# voice_caller.net
KiCad netlist of a schematic drawn in EAGLE
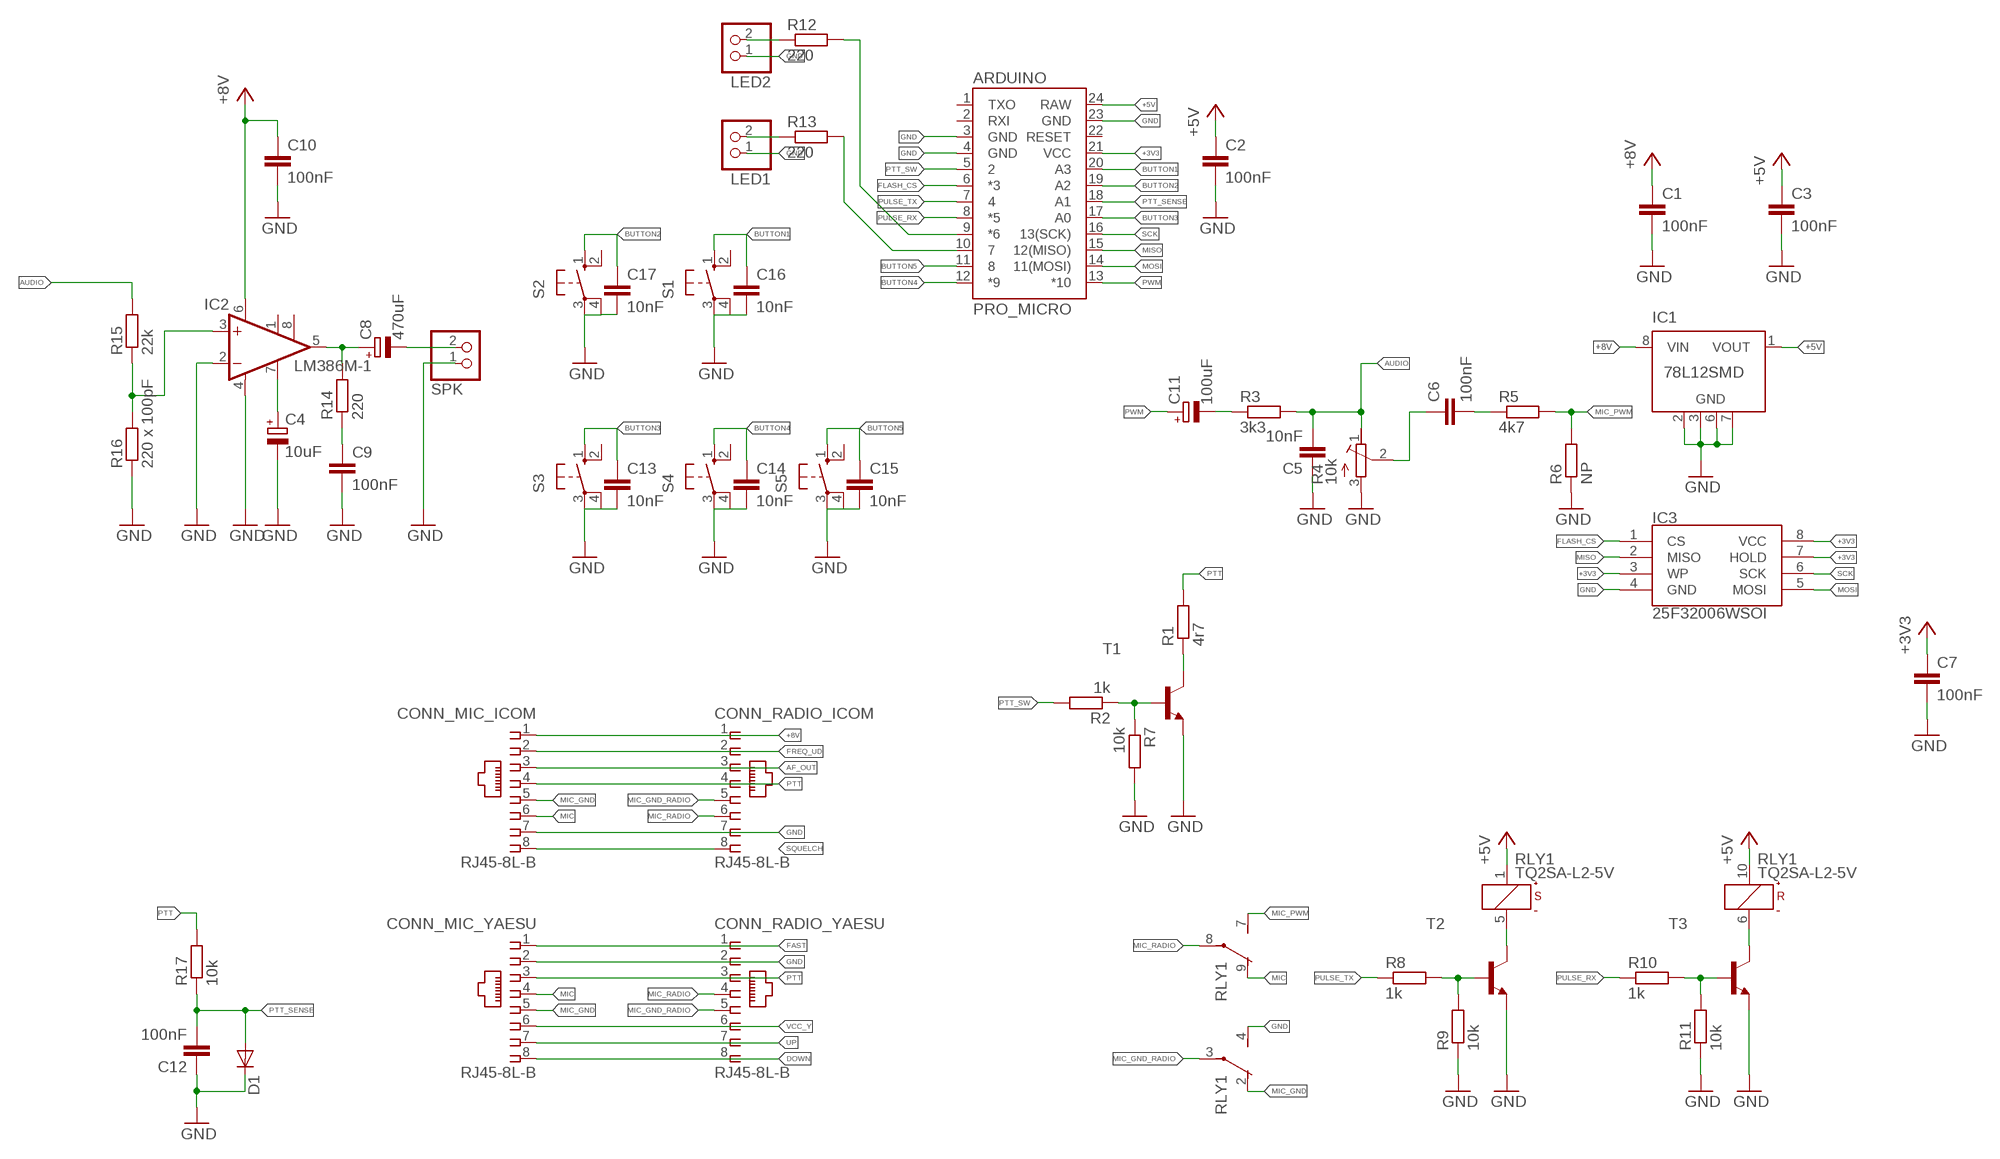
[diagram p0: schematic, sheet 1]

(export (version "E")
  (design (tool "Eeschema 10.0.6"))
  (components
    (comp (ref "ARDUINO")
      (value "PRO_MICRO")
      (footprint "eagle-import:SPARKFUN_PRO_MICRO")
      (libsource (lib "eagle-import") (part "SPARKFUN_PRO_MICRO"))
    )
    (comp (ref "C1")
      (value "100nF")
      (footprint "eagle-import:C1206K")
      (libsource (lib "eagle-import") (part "C-EUC1206K"))
    )
    (comp (ref "C2")
      (value "100nF")
      (footprint "eagle-import:C1206K")
      (libsource (lib "eagle-import") (part "C-EUC1206K"))
    )
    (comp (ref "C3")
      (value "100nF")
      (footprint "eagle-import:C1206K")
      (libsource (lib "eagle-import") (part "C-EUC1206K"))
    )
    (comp (ref "C4")
      (value "10uF")
      (footprint "eagle-import:E2,5-6")
      (libsource (lib "eagle-import") (part "CPOL-EUE2.5-6"))
    )
    (comp (ref "C5")
      (value "10nF")
      (footprint "eagle-import:C1206K")
      (libsource (lib "eagle-import") (part "C-EUC1206K"))
    )
    (comp (ref "C6")
      (value "100nF")
      (footprint "eagle-import:C1206K")
      (libsource (lib "eagle-import") (part "C-EUC1206K"))
    )
    (comp (ref "C7")
      (value "100nF")
      (footprint "eagle-import:C1206K")
      (libsource (lib "eagle-import") (part "C-EUC1206K"))
    )
    (comp (ref "C8")
      (value "470uF")
      (footprint "eagle-import:E2,5-6")
      (libsource (lib "eagle-import") (part "CPOL-EUE2.5-6"))
    )
    (comp (ref "C9")
      (value "100nF")
      (footprint "eagle-import:C1206K")
      (libsource (lib "eagle-import") (part "C-EUC1206K"))
    )
    (comp (ref "C10")
      (value "100nF")
      (footprint "eagle-import:C1206K")
      (libsource (lib "eagle-import") (part "C-EUC1206K"))
    )
    (comp (ref "C11")
      (value "100uF")
      (footprint "eagle-import:E2,5-6")
      (libsource (lib "eagle-import") (part "CPOL-EUE2.5-6"))
    )
    (comp (ref "C12")
      (value "100nF")
      (footprint "eagle-import:C1206K")
      (libsource (lib "eagle-import") (part "C-EUC1206K"))
    )
    (comp (ref "C13")
      (value "10nF")
      (footprint "eagle-import:C1206K")
      (libsource (lib "eagle-import") (part "C-EUC1206K"))
    )
    (comp (ref "C14")
      (value "10nF")
      (footprint "eagle-import:C1206K")
      (libsource (lib "eagle-import") (part "C-EUC1206K"))
    )
    (comp (ref "C15")
      (value "10nF")
      (footprint "eagle-import:C1206K")
      (libsource (lib "eagle-import") (part "C-EUC1206K"))
    )
    (comp (ref "C16")
      (value "10nF")
      (footprint "eagle-import:C1206K")
      (libsource (lib "eagle-import") (part "C-EUC1206K"))
    )
    (comp (ref "C17")
      (value "10nF")
      (footprint "eagle-import:C1206K")
      (libsource (lib "eagle-import") (part "C-EUC1206K"))
    )
    (comp (ref "CONN_MIC_ICOM")
      (value "RJ45-8L-B")
      (footprint "eagle-import:RJ45-NO-SHIELD")
      (fields (field (name "MF") "TYCO ELECTRONICS"))
      (libsource (lib "eagle-import") (part "RJ45-8L-B"))
    )
    (comp (ref "CONN_MIC_YAESU")
      (value "RJ45-8L-B")
      (footprint "eagle-import:RJ45-NO-SHIELD")
      (fields (field (name "MF") "TYCO ELECTRONICS"))
      (libsource (lib "eagle-import") (part "RJ45-8L-B"))
    )
    (comp (ref "CONN_RADIO_ICOM")
      (value "RJ45-8L-B")
      (footprint "eagle-import:RJ45-NO-SHIELD")
      (fields (field (name "MF") "TYCO ELECTRONICS"))
      (libsource (lib "eagle-import") (part "RJ45-8L-B"))
    )
    (comp (ref "CONN_RADIO_YAESU")
      (value "RJ45-8L-B")
      (footprint "eagle-import:RJ45-NO-SHIELD")
      (fields (field (name "MF") "TYCO ELECTRONICS"))
      (libsource (lib "eagle-import") (part "RJ45-8L-B"))
    )
    (comp (ref "D1")
      (value "DIODE-SOD80C")
      (footprint "eagle-import:SOD80C")
      (libsource (lib "eagle-import") (part "DIODE-SOD80C"))
    )
    (comp (ref "IC1")
      (value "78L12SMD")
      (footprint "eagle-import:SO08")
      (libsource (lib "eagle-import") (part "78LSMD12"))
    )
    (comp (ref "IC2")
      (value "LM386M-1")
      (footprint "eagle-import:SO08")
      (libsource (lib "eagle-import") (part "LM386?-M1"))
    )
    (comp (ref "IC3")
      (value "25F32006WSOI")
      (footprint "eagle-import:SO08-EIAJ")
      (libsource (lib "eagle-import") (part "SPI_FLASH-X25XXSMD1"))
    )
    (comp (ref "LED1")
      (value "PINHD-1X2")
      (footprint "eagle-import:1X02")
      (libsource (lib "eagle-import") (part "PINHD-1X2"))
    )
    (comp (ref "LED2")
      (value "PINHD-1X2")
      (footprint "eagle-import:1X02")
      (libsource (lib "eagle-import") (part "PINHD-1X2"))
    )
    (comp (ref "R1")
      (value "4r7")
      (footprint "eagle-import:M1206")
      (libsource (lib "eagle-import") (part "R-EU_M1206"))
    )
    (comp (ref "R2")
      (value "1k")
      (footprint "eagle-import:M1206")
      (libsource (lib "eagle-import") (part "R-EU_M1206"))
    )
    (comp (ref "R3")
      (value "3k3")
      (footprint "eagle-import:M1206")
      (libsource (lib "eagle-import") (part "R-EU_M1206"))
    )
    (comp (ref "R4")
      (value "10k")
      (footprint "eagle-import:RTRIMT93XB")
      (libsource (lib "eagle-import") (part "R-TRIMMT93XB"))
    )
    (comp (ref "R5")
      (value "4k7")
      (footprint "eagle-import:M1206")
      (libsource (lib "eagle-import") (part "R-EU_M1206"))
    )
    (comp (ref "R6")
      (value "NP")
      (footprint "eagle-import:M1206")
      (libsource (lib "eagle-import") (part "R-EU_M1206"))
    )
    (comp (ref "R7")
      (value "10k")
      (footprint "eagle-import:M1206")
      (libsource (lib "eagle-import") (part "R-EU_M1206"))
    )
    (comp (ref "R8")
      (value "1k")
      (footprint "eagle-import:M1206")
      (libsource (lib "eagle-import") (part "R-EU_M1206"))
    )
    (comp (ref "R9")
      (value "10k")
      (footprint "eagle-import:M1206")
      (libsource (lib "eagle-import") (part "R-EU_M1206"))
    )
    (comp (ref "R10")
      (value "1k")
      (footprint "eagle-import:M1206")
      (libsource (lib "eagle-import") (part "R-EU_M1206"))
    )
    (comp (ref "R11")
      (value "10k")
      (footprint "eagle-import:M1206")
      (libsource (lib "eagle-import") (part "R-EU_M1206"))
    )
    (comp (ref "R12")
      (value "220")
      (footprint "eagle-import:M1206")
      (libsource (lib "eagle-import") (part "R-EU_M1206"))
    )
    (comp (ref "R13")
      (value "220")
      (footprint "eagle-import:M1206")
      (libsource (lib "eagle-import") (part "R-EU_M1206"))
    )
    (comp (ref "R14")
      (value "220")
      (footprint "eagle-import:M1206")
      (libsource (lib "eagle-import") (part "R-EU_M1206"))
    )
    (comp (ref "R15")
      (value "22k")
      (footprint "eagle-import:M1206")
      (libsource (lib "eagle-import") (part "R-EU_M1206"))
    )
    (comp (ref "R16")
      (value "220 x 100pF")
      (footprint "eagle-import:M1206")
      (libsource (lib "eagle-import") (part "R-EU_M1206"))
    )
    (comp (ref "R17")
      (value "10k")
      (footprint "eagle-import:M1206")
      (libsource (lib "eagle-import") (part "R-EU_M1206"))
    )
    (comp (ref "RLY1")
      (value "TQ2SA-L2-5V")
      (footprint "eagle-import:TQ-SA")
      (fields (field (name "MF") "AROMAT/ MATSUSHITA"))
      (libsource (lib "eagle-import") (part "TQ2?-L2-SA5V"))
    )
    (comp (ref "S1")
      (value "10-XX")
      (footprint "eagle-import:B3F-10XX")
      (fields (field (name "MPN") "B3F-1000"))
      (libsource (lib "eagle-import") (part "10-XX"))
    )
    (comp (ref "S2")
      (value "10-XX")
      (footprint "eagle-import:B3F-10XX")
      (fields (field (name "MPN") "B3F-1000"))
      (libsource (lib "eagle-import") (part "10-XX"))
    )
    (comp (ref "S3")
      (value "10-XX")
      (footprint "eagle-import:B3F-10XX")
      (fields (field (name "MPN") "B3F-1000"))
      (libsource (lib "eagle-import") (part "10-XX"))
    )
    (comp (ref "S4")
      (value "10-XX")
      (footprint "eagle-import:B3F-10XX")
      (fields (field (name "MPN") "B3F-1000"))
      (libsource (lib "eagle-import") (part "10-XX"))
    )
    (comp (ref "S5")
      (value "10-XX")
      (footprint "eagle-import:B3F-10XX")
      (fields (field (name "MPN") "B3F-1000"))
      (libsource (lib "eagle-import") (part "10-XX"))
    )
    (comp (ref "SPK")
      (value "PINHD-1X2")
      (footprint "eagle-import:1X02")
      (libsource (lib "eagle-import") (part "PINHD-1X2"))
    )
    (comp (ref "T1")
      (value "MMBT3904LT1-NPN-SOT23-BEC")
      (footprint "eagle-import:SOT23-BEC")
      (libsource (lib "eagle-import") (part "-NPN-SOT23-BECMMBT3904LT1"))
    )
    (comp (ref "T2")
      (value "MMBT3904LT1-NPN-SOT23-BEC")
      (footprint "eagle-import:SOT23-BEC")
      (libsource (lib "eagle-import") (part "-NPN-SOT23-BECMMBT3904LT1"))
    )
    (comp (ref "T3")
      (value "MMBT3904LT1-NPN-SOT23-BEC")
      (footprint "eagle-import:SOT23-BEC")
      (libsource (lib "eagle-import") (part "-NPN-SOT23-BECMMBT3904LT1"))
    )
  )
  (nets
    (net (code "1") (name "+3V3") (class "Default")
      (node (ref "ARDUINO") (pin "21") (pinfunction "VCC_21") (pintype "power_in"))
      (node (ref "C7") (pin "1") (pinfunction "1_1") (pintype "passive"))
      (node (ref "IC3") (pin "3") (pinfunction "WP_3") (pintype "bidirectional"))
      (node (ref "IC3") (pin "7") (pinfunction "HOLD_7") (pintype "bidirectional"))
      (node (ref "IC3") (pin "8") (pinfunction "VCC_8") (pintype "power_in"))
    )
    (net (code "2") (name "+5V") (class "Default")
      (node (ref "ARDUINO") (pin "24") (pinfunction "RAW_24") (pintype "power_in"))
      (node (ref "C2") (pin "1") (pinfunction "1_1") (pintype "passive"))
      (node (ref "C3") (pin "1") (pinfunction "1_1") (pintype "passive"))
      (node (ref "IC1") (pin "1") (pinfunction "VOUT_1") (pintype "output"))
      (node (ref "RLY1") (pin "1") (pinfunction "+_1") (pintype "passive"))
      (node (ref "RLY1") (pin "10") (pinfunction "+_10") (pintype "passive"))
    )
    (net (code "3") (name "+8V") (class "Default")
      (node (ref "C1") (pin "1") (pinfunction "1_1") (pintype "passive"))
      (node (ref "C10") (pin "1") (pinfunction "1_1") (pintype "passive"))
      (node (ref "CONN_MIC_ICOM") (pin "1") (pinfunction "1_1") (pintype "passive"))
      (node (ref "CONN_RADIO_ICOM") (pin "1") (pinfunction "1_1") (pintype "passive"))
      (node (ref "IC1") (pin "8") (pinfunction "VIN_8") (pintype "passive"))
      (node (ref "IC2") (pin "6") (pinfunction "VS_6") (pintype "power_in"))
    )
    (net (code "4") (name "AF_OUT") (class "Default")
      (node (ref "CONN_MIC_ICOM") (pin "3") (pinfunction "3_3") (pintype "passive"))
      (node (ref "CONN_RADIO_ICOM") (pin "3") (pinfunction "3_3") (pintype "passive"))
    )
    (net (code "5") (name "AUDIO") (class "Default")
      (node (ref "C5") (pin "2") (pinfunction "2_2") (pintype "passive"))
      (node (ref "R15") (pin "2") (pinfunction "2_2") (pintype "passive"))
      (node (ref "R3") (pin "2") (pinfunction "2_2") (pintype "passive"))
      (node (ref "R4") (pin "1") (pinfunction "E_1") (pintype "passive"))
    )
    (net (code "6") (name "BUTTON1") (class "Default")
      (node (ref "ARDUINO") (pin "20") (pinfunction "A3_20") (pintype "bidirectional"))
      (node (ref "C16") (pin "1") (pinfunction "1_1") (pintype "passive"))
      (node (ref "S1") (pin "1") (pinfunction "S_1") (pintype "passive"))
    )
    (net (code "7") (name "BUTTON2") (class "Default")
      (node (ref "ARDUINO") (pin "19") (pinfunction "A2_19") (pintype "bidirectional"))
      (node (ref "C17") (pin "1") (pinfunction "1_1") (pintype "passive"))
      (node (ref "S2") (pin "1") (pinfunction "S_1") (pintype "passive"))
    )
    (net (code "8") (name "BUTTON3") (class "Default")
      (node (ref "ARDUINO") (pin "17") (pinfunction "A0_17") (pintype "bidirectional"))
      (node (ref "C13") (pin "1") (pinfunction "1_1") (pintype "passive"))
      (node (ref "S3") (pin "1") (pinfunction "S_1") (pintype "passive"))
    )
    (net (code "9") (name "BUTTON4") (class "Default")
      (node (ref "ARDUINO") (pin "12") (pinfunction "*9_12") (pintype "bidirectional"))
      (node (ref "C14") (pin "1") (pinfunction "1_1") (pintype "passive"))
      (node (ref "S4") (pin "1") (pinfunction "S_1") (pintype "passive"))
    )
    (net (code "10") (name "BUTTON5") (class "Default")
      (node (ref "ARDUINO") (pin "11") (pinfunction "8_11") (pintype "bidirectional"))
      (node (ref "C15") (pin "1") (pinfunction "1_1") (pintype "passive"))
      (node (ref "S5") (pin "1") (pinfunction "S_1") (pintype "passive"))
    )
    (net (code "11") (name "DOWN") (class "Default")
      (node (ref "CONN_MIC_YAESU") (pin "8") (pinfunction "8_8") (pintype "passive"))
      (node (ref "CONN_RADIO_YAESU") (pin "8") (pinfunction "8_8") (pintype "passive"))
    )
    (net (code "12") (name "FAST") (class "Default")
      (node (ref "CONN_MIC_YAESU") (pin "1") (pinfunction "1_1") (pintype "passive"))
      (node (ref "CONN_RADIO_YAESU") (pin "1") (pinfunction "1_1") (pintype "passive"))
    )
    (net (code "13") (name "FLASH_CS") (class "Default")
      (node (ref "ARDUINO") (pin "6") (pinfunction "*3_6") (pintype "bidirectional"))
      (node (ref "IC3") (pin "1") (pinfunction "CS_1") (pintype "bidirectional"))
    )
    (net (code "14") (name "FREQ_UD") (class "Default")
      (node (ref "CONN_MIC_ICOM") (pin "2") (pinfunction "2_2") (pintype "passive"))
      (node (ref "CONN_RADIO_ICOM") (pin "2") (pinfunction "2_2") (pintype "passive"))
    )
    (net (code "15") (name "GND") (class "Default")
      (node (ref "ARDUINO") (pin "23") (pinfunction "GND_23") (pintype "power_in"))
      (node (ref "ARDUINO") (pin "3") (pinfunction "GND_3") (pintype "power_in"))
      (node (ref "ARDUINO") (pin "4") (pinfunction "GND_4") (pintype "power_in"))
      (node (ref "C1") (pin "2") (pinfunction "2_2") (pintype "passive"))
      (node (ref "C10") (pin "2") (pinfunction "2_2") (pintype "passive"))
      (node (ref "C12") (pin "1") (pinfunction "1_1") (pintype "passive"))
      (node (ref "C13") (pin "2") (pinfunction "2_2") (pintype "passive"))
      (node (ref "C14") (pin "2") (pinfunction "2_2") (pintype "passive"))
      (node (ref "C15") (pin "2") (pinfunction "2_2") (pintype "passive"))
      (node (ref "C16") (pin "2") (pinfunction "2_2") (pintype "passive"))
      (node (ref "C17") (pin "2") (pinfunction "2_2") (pintype "passive"))
      (node (ref "C2") (pin "2") (pinfunction "2_2") (pintype "passive"))
      (node (ref "C3") (pin "2") (pinfunction "2_2") (pintype "passive"))
      (node (ref "C4") (pin "-") (pinfunction "-_-") (pintype "passive"))
      (node (ref "C5") (pin "1") (pinfunction "1_1") (pintype "passive"))
      (node (ref "C7") (pin "2") (pinfunction "2_2") (pintype "passive"))
      (node (ref "C9") (pin "2") (pinfunction "2_2") (pintype "passive"))
      (node (ref "CONN_MIC_ICOM") (pin "7") (pinfunction "7_7") (pintype "passive"))
      (node (ref "CONN_MIC_YAESU") (pin "2") (pinfunction "2_2") (pintype "passive"))
      (node (ref "CONN_RADIO_ICOM") (pin "7") (pinfunction "7_7") (pintype "passive"))
      (node (ref "CONN_RADIO_YAESU") (pin "2") (pinfunction "2_2") (pintype "passive"))
      (node (ref "D1") (pin "C") (pinfunction "C_C") (pintype "passive"))
      (node (ref "IC1") (pin "2") (pinfunction "GND_2") (pintype "power_in"))
      (node (ref "IC1") (pin "3") (pinfunction "GND_3") (pintype "power_in"))
      (node (ref "IC1") (pin "6") (pinfunction "GND_6") (pintype "power_in"))
      (node (ref "IC1") (pin "7") (pinfunction "GND_7") (pintype "power_in"))
      (node (ref "IC2") (pin "2") (pinfunction "-IN_2") (pintype "input"))
      (node (ref "IC2") (pin "4") (pinfunction "GND_4") (pintype "power_in"))
      (node (ref "IC3") (pin "4") (pinfunction "GND_4") (pintype "power_in"))
      (node (ref "LED1") (pin "1") (pinfunction "1_1") (pintype "passive"))
      (node (ref "LED2") (pin "1") (pinfunction "1_1") (pintype "passive"))
      (node (ref "R11") (pin "1") (pinfunction "1_1") (pintype "passive"))
      (node (ref "R16") (pin "1") (pinfunction "1_1") (pintype "passive"))
      (node (ref "R4") (pin "3") (pinfunction "A_3") (pintype "passive"))
      (node (ref "R6") (pin "1") (pinfunction "1_1") (pintype "passive"))
      (node (ref "R7") (pin "2") (pinfunction "2_2") (pintype "passive"))
      (node (ref "R9") (pin "1") (pinfunction "1_1") (pintype "passive"))
      (node (ref "RLY1") (pin "4") (pinfunction "S_4") (pintype "passive"))
      (node (ref "S1") (pin "3") (pinfunction "P_3") (pintype "passive"))
      (node (ref "S1") (pin "4") (pinfunction "P1_4") (pintype "passive"))
      (node (ref "S2") (pin "3") (pinfunction "P_3") (pintype "passive"))
      (node (ref "S2") (pin "4") (pinfunction "P1_4") (pintype "passive"))
      (node (ref "S3") (pin "3") (pinfunction "P_3") (pintype "passive"))
      (node (ref "S3") (pin "4") (pinfunction "P1_4") (pintype "passive"))
      (node (ref "S4") (pin "3") (pinfunction "P_3") (pintype "passive"))
      (node (ref "S4") (pin "4") (pinfunction "P1_4") (pintype "passive"))
      (node (ref "S5") (pin "3") (pinfunction "P_3") (pintype "passive"))
      (node (ref "S5") (pin "4") (pinfunction "P1_4") (pintype "passive"))
      (node (ref "SPK") (pin "1") (pinfunction "1_1") (pintype "passive"))
      (node (ref "T1") (pin "E") (pinfunction "E_E") (pintype "passive"))
      (node (ref "T2") (pin "E") (pinfunction "E_E") (pintype "passive"))
      (node (ref "T3") (pin "E") (pinfunction "E_E") (pintype "passive"))
    )
    (net (code "16") (name "MIC") (class "Default")
      (node (ref "CONN_MIC_ICOM") (pin "6") (pinfunction "6_6") (pintype "passive"))
      (node (ref "CONN_MIC_YAESU") (pin "4") (pinfunction "4_4") (pintype "passive"))
      (node (ref "RLY1") (pin "9") (pinfunction "O_9") (pintype "passive"))
    )
    (net (code "17") (name "MIC_GND") (class "Default")
      (node (ref "CONN_MIC_ICOM") (pin "5") (pinfunction "5_5") (pintype "passive"))
      (node (ref "CONN_MIC_YAESU") (pin "5") (pinfunction "5_5") (pintype "passive"))
      (node (ref "RLY1") (pin "2") (pinfunction "O_2") (pintype "passive"))
    )
    (net (code "18") (name "MIC_GND_RADIO") (class "Default")
      (node (ref "CONN_RADIO_ICOM") (pin "5") (pinfunction "5_5") (pintype "passive"))
      (node (ref "CONN_RADIO_YAESU") (pin "5") (pinfunction "5_5") (pintype "passive"))
      (node (ref "RLY1") (pin "3") (pinfunction "P_3") (pintype "passive"))
    )
    (net (code "19") (name "MIC_PWM") (class "Default")
      (node (ref "R5") (pin "2") (pinfunction "2_2") (pintype "passive"))
      (node (ref "R6") (pin "2") (pinfunction "2_2") (pintype "passive"))
      (node (ref "RLY1") (pin "7") (pinfunction "S_7") (pintype "passive"))
    )
    (net (code "20") (name "MIC_RADIO") (class "Default")
      (node (ref "CONN_RADIO_ICOM") (pin "6") (pinfunction "6_6") (pintype "passive"))
      (node (ref "CONN_RADIO_YAESU") (pin "4") (pinfunction "4_4") (pintype "passive"))
      (node (ref "RLY1") (pin "8") (pinfunction "P_8") (pintype "passive"))
    )
    (net (code "21") (name "MISO") (class "Default")
      (node (ref "ARDUINO") (pin "15") (pinfunction "12(MISO)_15") (pintype "bidirectional"))
      (node (ref "IC3") (pin "2") (pinfunction "MISO_2") (pintype "bidirectional"))
    )
    (net (code "22") (name "MOSI") (class "Default")
      (node (ref "ARDUINO") (pin "14") (pinfunction "11(MOSI)_14") (pintype "bidirectional"))
      (node (ref "IC3") (pin "5") (pinfunction "MOSI_5") (pintype "bidirectional"))
    )
    (net (code "23") (name "Net-(ARDUINO-*6)") (class "Default")
      (node (ref "ARDUINO") (pin "9") (pinfunction "*6_9") (pintype "bidirectional"))
      (node (ref "R12") (pin "2") (pinfunction "2_2") (pintype "passive"))
    )
    (net (code "24") (name "Net-(ARDUINO-7)") (class "Default")
      (node (ref "ARDUINO") (pin "10") (pinfunction "7_10") (pintype "bidirectional"))
      (node (ref "R13") (pin "2") (pinfunction "2_2") (pintype "passive"))
    )
    (net (code "25") (name "Net-(C6-Pad2)") (class "Default")
      (node (ref "C6") (pin "2") (pinfunction "2_2") (pintype "passive"))
      (node (ref "R5") (pin "1") (pinfunction "1_1") (pintype "passive"))
    )
    (net (code "26") (name "Net-(C8-Pad-)") (class "Default")
      (node (ref "C8") (pin "-") (pinfunction "-_-") (pintype "passive"))
      (node (ref "SPK") (pin "2") (pinfunction "2_2") (pintype "passive"))
    )
    (net (code "27") (name "Net-(C9-Pad1)") (class "Default")
      (node (ref "C9") (pin "1") (pinfunction "1_1") (pintype "passive"))
      (node (ref "R14") (pin "1") (pinfunction "1_1") (pintype "passive"))
    )
    (net (code "28") (name "Net-(C11-Pad-)") (class "Default")
      (node (ref "C11") (pin "-") (pinfunction "-_-") (pintype "passive"))
      (node (ref "R3") (pin "1") (pinfunction "1_1") (pintype "passive"))
    )
    (net (code "29") (name "Net-(IC2-+IN)") (class "Default")
      (node (ref "IC2") (pin "3") (pinfunction "+IN_3") (pintype "input"))
      (node (ref "R15") (pin "1") (pinfunction "1_1") (pintype "passive"))
      (node (ref "R16") (pin "2") (pinfunction "2_2") (pintype "passive"))
    )
    (net (code "30") (name "Net-(IC2-BYPASS)") (class "Default")
      (node (ref "C4") (pin "+") (pinfunction "+_+") (pintype "passive"))
      (node (ref "IC2") (pin "7") (pinfunction "BYPASS_7") (pintype "passive"))
    )
    (net (code "31") (name "Net-(IC2-OUT)") (class "Default")
      (node (ref "C8") (pin "+") (pinfunction "+_+") (pintype "passive"))
      (node (ref "IC2") (pin "5") (pinfunction "OUT_5") (pintype "output"))
      (node (ref "R14") (pin "2") (pinfunction "2_2") (pintype "passive"))
    )
    (net (code "32") (name "Net-(LED1-Pad2)") (class "Default")
      (node (ref "LED1") (pin "2") (pinfunction "2_2") (pintype "passive"))
      (node (ref "R13") (pin "1") (pinfunction "1_1") (pintype "passive"))
    )
    (net (code "33") (name "Net-(LED2-Pad2)") (class "Default")
      (node (ref "LED2") (pin "2") (pinfunction "2_2") (pintype "passive"))
      (node (ref "R12") (pin "1") (pinfunction "1_1") (pintype "passive"))
    )
    (net (code "34") (name "Net-(R1-Pad1)") (class "Default")
      (node (ref "R1") (pin "1") (pinfunction "1_1") (pintype "passive"))
      (node (ref "T1") (pin "C") (pinfunction "C_C") (pintype "passive"))
    )
    (net (code "35") (name "Net-(R2-Pad1)") (class "Default")
      (node (ref "R2") (pin "1") (pinfunction "1_1") (pintype "passive"))
      (node (ref "R7") (pin "1") (pinfunction "1_1") (pintype "passive"))
      (node (ref "T1") (pin "B") (pinfunction "B_B") (pintype "passive"))
    )
    (net (code "36") (name "Net-(R4-S)") (class "Default")
      (node (ref "C6") (pin "1") (pinfunction "1_1") (pintype "passive"))
      (node (ref "R4") (pin "2") (pinfunction "S_2") (pintype "passive"))
    )
    (net (code "37") (name "Net-(R8-Pad2)") (class "Default")
      (node (ref "R8") (pin "2") (pinfunction "2_2") (pintype "passive"))
      (node (ref "R9") (pin "2") (pinfunction "2_2") (pintype "passive"))
      (node (ref "T2") (pin "B") (pinfunction "B_B") (pintype "passive"))
    )
    (net (code "38") (name "Net-(R10-Pad2)") (class "Default")
      (node (ref "R10") (pin "2") (pinfunction "2_2") (pintype "passive"))
      (node (ref "R11") (pin "2") (pinfunction "2_2") (pintype "passive"))
      (node (ref "T3") (pin "B") (pinfunction "B_B") (pintype "passive"))
    )
    (net (code "39") (name "Net-(RLY1C--)") (class "Default")
      (node (ref "RLY1") (pin "6") (pinfunction "-_6") (pintype "passive"))
      (node (ref "T3") (pin "C") (pinfunction "C_C") (pintype "passive"))
    )
    (net (code "40") (name "Net-(RLY1D--)") (class "Default")
      (node (ref "RLY1") (pin "5") (pinfunction "-_5") (pintype "passive"))
      (node (ref "T2") (pin "C") (pinfunction "C_C") (pintype "passive"))
    )
    (net (code "41") (name "PTT") (class "Default")
      (node (ref "CONN_MIC_ICOM") (pin "4") (pinfunction "4_4") (pintype "passive"))
      (node (ref "CONN_MIC_YAESU") (pin "3") (pinfunction "3_3") (pintype "passive"))
      (node (ref "CONN_RADIO_ICOM") (pin "4") (pinfunction "4_4") (pintype "passive"))
      (node (ref "CONN_RADIO_YAESU") (pin "3") (pinfunction "3_3") (pintype "passive"))
      (node (ref "R1") (pin "2") (pinfunction "2_2") (pintype "passive"))
      (node (ref "R17") (pin "2") (pinfunction "2_2") (pintype "passive"))
    )
    (net (code "42") (name "PTT_SENSE") (class "Default")
      (node (ref "ARDUINO") (pin "18") (pinfunction "A1_18") (pintype "bidirectional"))
      (node (ref "C12") (pin "2") (pinfunction "2_2") (pintype "passive"))
      (node (ref "D1") (pin "A") (pinfunction "A_A") (pintype "passive"))
      (node (ref "R17") (pin "1") (pinfunction "1_1") (pintype "passive"))
    )
    (net (code "43") (name "PTT_SW") (class "Default")
      (node (ref "ARDUINO") (pin "5") (pinfunction "2_5") (pintype "bidirectional"))
      (node (ref "R2") (pin "2") (pinfunction "2_2") (pintype "passive"))
    )
    (net (code "44") (name "PULSE_RX") (class "Default")
      (node (ref "ARDUINO") (pin "8") (pinfunction "*5_8") (pintype "bidirectional"))
      (node (ref "R10") (pin "1") (pinfunction "1_1") (pintype "passive"))
    )
    (net (code "45") (name "PULSE_TX") (class "Default")
      (node (ref "ARDUINO") (pin "7") (pinfunction "4_7") (pintype "bidirectional"))
      (node (ref "R8") (pin "1") (pinfunction "1_1") (pintype "passive"))
    )
    (net (code "46") (name "PWM") (class "Default")
      (node (ref "ARDUINO") (pin "13") (pinfunction "*10_13") (pintype "bidirectional"))
      (node (ref "C11") (pin "+") (pinfunction "+_+") (pintype "passive"))
    )
    (net (code "47") (name "SCK") (class "Default")
      (node (ref "ARDUINO") (pin "16") (pinfunction "13(SCK)_16") (pintype "bidirectional"))
      (node (ref "IC3") (pin "6") (pinfunction "SCK_6") (pintype "bidirectional"))
    )
    (net (code "48") (name "SQUELCH") (class "Default")
      (node (ref "CONN_MIC_ICOM") (pin "8") (pinfunction "8_8") (pintype "passive"))
      (node (ref "CONN_RADIO_ICOM") (pin "8") (pinfunction "8_8") (pintype "passive"))
    )
    (net (code "49") (name "UP") (class "Default")
      (node (ref "CONN_MIC_YAESU") (pin "7") (pinfunction "7_7") (pintype "passive"))
      (node (ref "CONN_RADIO_YAESU") (pin "7") (pinfunction "7_7") (pintype "passive"))
    )
    (net (code "50") (name "VCC_Y") (class "Default")
      (node (ref "CONN_MIC_YAESU") (pin "6") (pinfunction "6_6") (pintype "passive"))
      (node (ref "CONN_RADIO_YAESU") (pin "6") (pinfunction "6_6") (pintype "passive"))
    )
    (net (code "51") (name "unconnected-(ARDUINO-RESET-Pad22)") (class "Default")
      (node (ref "ARDUINO") (pin "22") (pinfunction "RESET_22") (pintype "bidirectional"))
    )
    (net (code "52") (name "unconnected-(ARDUINO-RXI-Pad2)") (class "Default")
      (node (ref "ARDUINO") (pin "2") (pinfunction "RXI_2") (pintype "bidirectional"))
    )
    (net (code "53") (name "unconnected-(ARDUINO-TXO-Pad1)") (class "Default")
      (node (ref "ARDUINO") (pin "1") (pinfunction "TXO_1") (pintype "bidirectional"))
    )
    (net (code "54") (name "unconnected-(IC2-GAIN-Pad1)") (class "Default")
      (node (ref "IC2") (pin "1") (pinfunction "GAIN_1") (pintype "passive"))
    )
    (net (code "55") (name "unconnected-(IC2-GAIN-Pad8)") (class "Default")
      (node (ref "IC2") (pin "8") (pinfunction "GAIN_8") (pintype "passive"))
    )
    (net (code "56") (name "unconnected-(S1-S1-Pad2)") (class "Default")
      (node (ref "S1") (pin "2") (pinfunction "S1_2") (pintype "passive"))
    )
    (net (code "57") (name "unconnected-(S2-S1-Pad2)") (class "Default")
      (node (ref "S2") (pin "2") (pinfunction "S1_2") (pintype "passive"))
    )
    (net (code "58") (name "unconnected-(S3-S1-Pad2)") (class "Default")
      (node (ref "S3") (pin "2") (pinfunction "S1_2") (pintype "passive"))
    )
    (net (code "59") (name "unconnected-(S4-S1-Pad2)") (class "Default")
      (node (ref "S4") (pin "2") (pinfunction "S1_2") (pintype "passive"))
    )
    (net (code "60") (name "unconnected-(S5-S1-Pad2)") (class "Default")
      (node (ref "S5") (pin "2") (pinfunction "S1_2") (pintype "passive"))
    )
  )
)
